# main.net
KiCad netlist of a schematic drawn in EAGLE
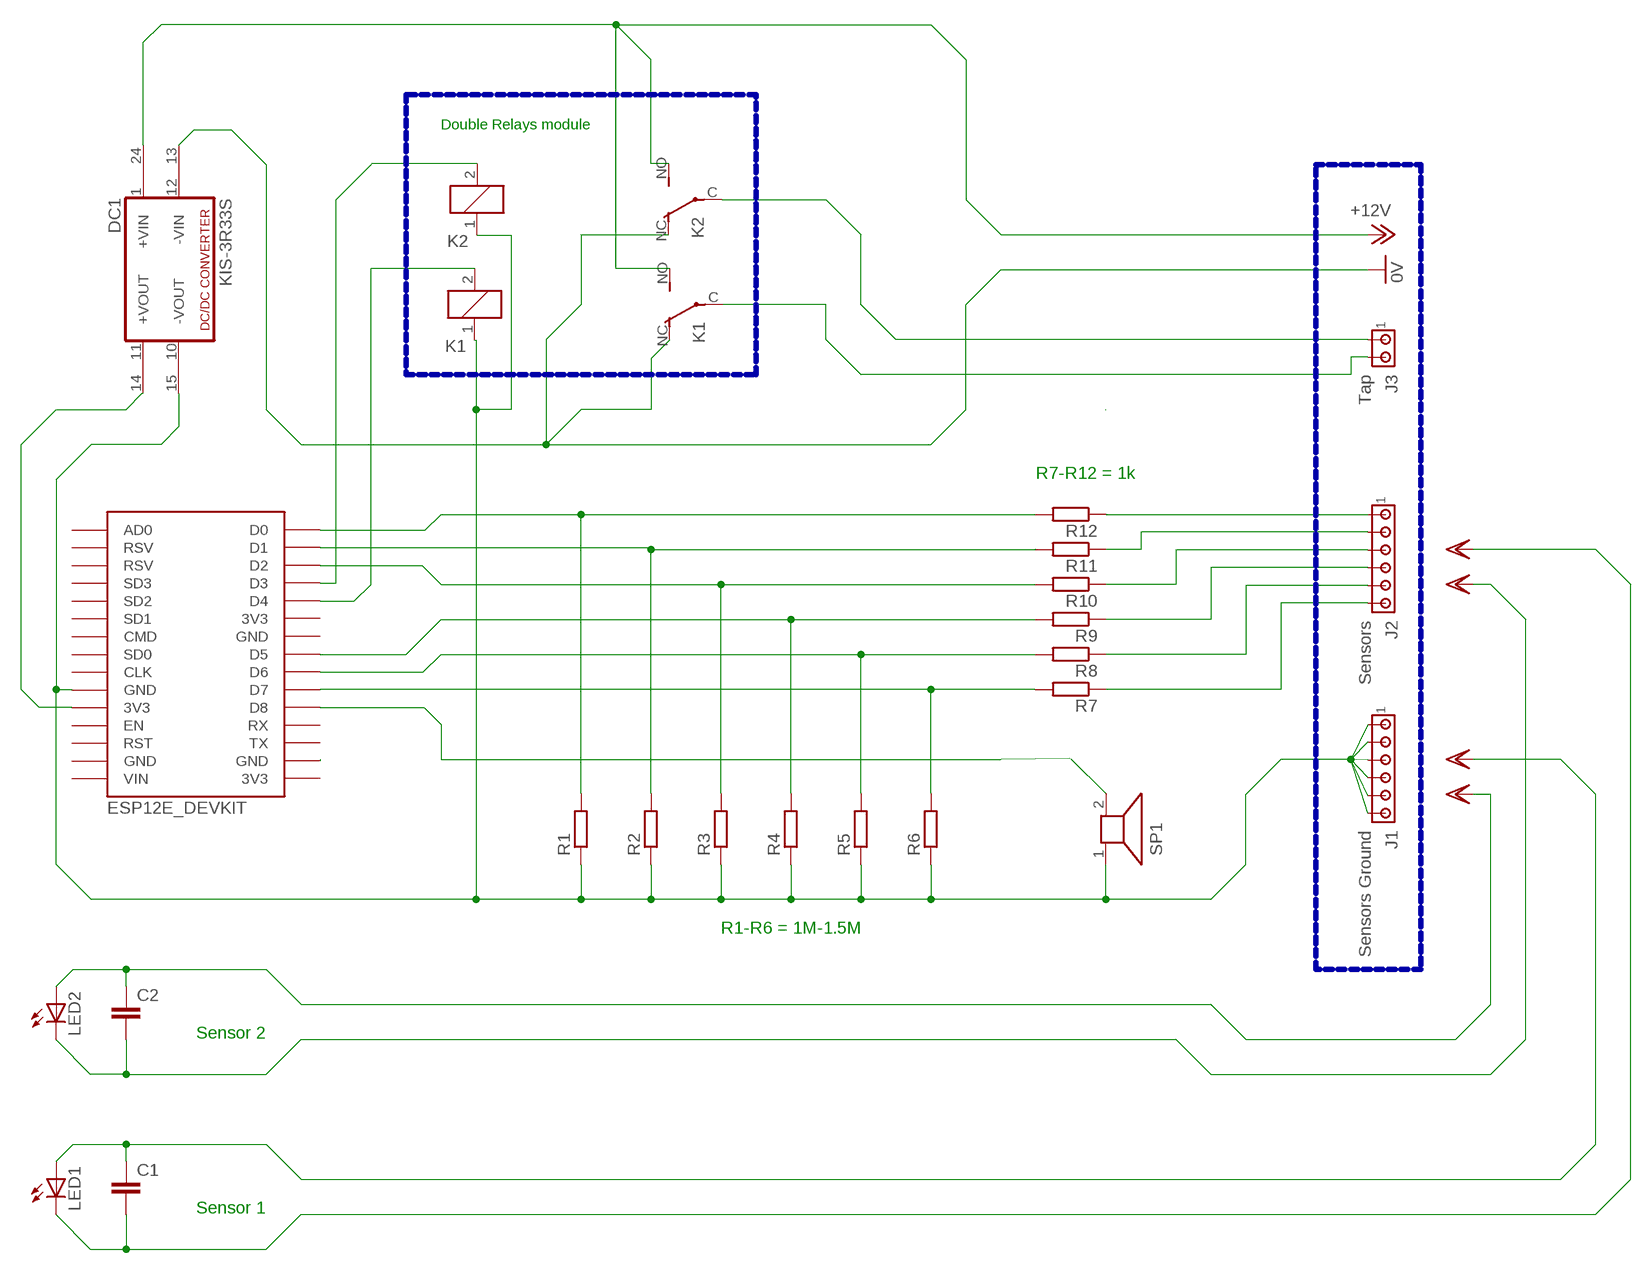
[diagram p0: schematic, sheet 1]

(export (version "E")
  (design (tool "Eeschema 10.0.6"))
  (components
    (comp (ref "C1")
      (value "C2,5-3")
      (footprint "eagle-import:C2.5-3")
      (libsource (lib "eagle-import") (part "C2,5-3"))
    )
    (comp (ref "C2")
      (value "C2,5-3")
      (footprint "eagle-import:C2.5-3")
      (libsource (lib "eagle-import") (part "C2,5-3"))
    )
    (comp (ref "DC1")
      (value "KIS-3R33S")
      (footprint "eagle-import:CMK")
      (libsource (lib "eagle-import") (part "DC213R"))
    )
    (comp (ref "J1")
      (value "Sensors Ground")
      (footprint "eagle-import:1X6MTA")
      (libsource (lib "eagle-import") (part "MTA06-156"))
    )
    (comp (ref "J2")
      (value "Sensors")
      (footprint "eagle-import:1X6MTA")
      (libsource (lib "eagle-import") (part "MTA06-156"))
    )
    (comp (ref "J3")
      (value "Tap")
      (footprint "eagle-import:1X2MTA")
      (libsource (lib "eagle-import") (part "MTA02-156"))
    )
    (comp (ref "K1")
      (value "CT112")
      (footprint "eagle-import:CT-SLIM")
      (libsource (lib "eagle-import") (part "CT112"))
    )
    (comp (ref "K2")
      (value "CT112")
      (footprint "eagle-import:CT-SLIM")
      (libsource (lib "eagle-import") (part "CT112"))
    )
    (comp (ref "LED1")
      (value "TLLG4400")
      (footprint "eagle-import:LED3MM")
      (fields (field (name "MF") "VISHAY SEMICONDUCTOR"))
      (libsource (lib "eagle-import") (part "TLLG4400"))
    )
    (comp (ref "LED2")
      (value "TLLG4400")
      (footprint "eagle-import:LED3MM")
      (fields (field (name "MF") "VISHAY SEMICONDUCTOR"))
      (libsource (lib "eagle-import") (part "TLLG4400"))
    )
    (comp (ref "R1")
      (value "R-EU_0204/7")
      (footprint "eagle-import:0204_7")
      (libsource (lib "eagle-import") (part "R-EU_0204/7"))
    )
    (comp (ref "R2")
      (value "R-EU_0204/7")
      (footprint "eagle-import:0204_7")
      (libsource (lib "eagle-import") (part "R-EU_0204/7"))
    )
    (comp (ref "R3")
      (value "R-EU_0204/7")
      (footprint "eagle-import:0204_7")
      (libsource (lib "eagle-import") (part "R-EU_0204/7"))
    )
    (comp (ref "R4")
      (value "R-EU_0204/7")
      (footprint "eagle-import:0204_7")
      (libsource (lib "eagle-import") (part "R-EU_0204/7"))
    )
    (comp (ref "R5")
      (value "R-EU_0204/7")
      (footprint "eagle-import:0204_7")
      (libsource (lib "eagle-import") (part "R-EU_0204/7"))
    )
    (comp (ref "R6")
      (value "R-EU_0204/7")
      (footprint "eagle-import:0204_7")
      (libsource (lib "eagle-import") (part "R-EU_0204/7"))
    )
    (comp (ref "R7")
      (value "R-EU_0204/7")
      (footprint "eagle-import:0204_7")
      (libsource (lib "eagle-import") (part "R-EU_0204/7"))
    )
    (comp (ref "R8")
      (value "R-EU_0204/7")
      (footprint "eagle-import:0204_7")
      (libsource (lib "eagle-import") (part "R-EU_0204/7"))
    )
    (comp (ref "R9")
      (value "R-EU_0204/7")
      (footprint "eagle-import:0204_7")
      (libsource (lib "eagle-import") (part "R-EU_0204/7"))
    )
    (comp (ref "R10")
      (value "R-EU_0204/7")
      (footprint "eagle-import:0204_7")
      (libsource (lib "eagle-import") (part "R-EU_0204/7"))
    )
    (comp (ref "R11")
      (value "R-EU_0204/7")
      (footprint "eagle-import:0204_7")
      (libsource (lib "eagle-import") (part "R-EU_0204/7"))
    )
    (comp (ref "R12")
      (value "R-EU_0204/7")
      (footprint "eagle-import:0204_7")
      (libsource (lib "eagle-import") (part "R-EU_0204/7"))
    )
    (comp (ref "SP1")
      (value "AL30P")
      (footprint "eagle-import:AL30P")
      (libsource (lib "eagle-import") (part "AL30P"))
    )
    (comp (ref "U$1")
      (value "ESP12E_DEVKIT")
      (footprint "eagle-import:ESP12E_DEVKIT")
      (libsource (lib "eagle-import") (part "ESP12E_DEVKIT"))
    )
  )
  (nets
    (net (code "1") (name "+12V") (class "Default")
      (node (ref "DC1") (pin "24") (pinfunction "+VIN1_24") (pintype "passive"))
      (node (ref "K1") (pin "NO") (pinfunction "S_NO") (pintype "passive"))
      (node (ref "K2") (pin "NO") (pinfunction "S_NO") (pintype "passive"))
    )
    (net (code "2") (name "0V") (class "Default")
      (node (ref "DC1") (pin "13") (pinfunction "-VIN1_13") (pintype "passive"))
      (node (ref "K1") (pin "NC") (pinfunction "O_NC") (pintype "passive"))
      (node (ref "K2") (pin "NC") (pinfunction "O_NC") (pintype "passive"))
    )
    (net (code "3") (name "Net-(DC1-+VOUT1)") (class "Default")
      (node (ref "DC1") (pin "14") (pinfunction "+VOUT1_14") (pintype "passive"))
      (node (ref "U$1") (pin "3V3@0") (pinfunction "3V3_3V3@0") (pintype "bidirectional"))
    )
    (net (code "4") (name "Net-(DC1--VOUT1)") (class "Default")
      (node (ref "DC1") (pin "15") (pinfunction "-VOUT1_15") (pintype "passive"))
      (node (ref "J1") (pin "1") (pinfunction "1_1") (pintype "passive"))
      (node (ref "J1") (pin "2") (pinfunction "2_2") (pintype "passive"))
      (node (ref "J1") (pin "3") (pinfunction "3_3") (pintype "passive"))
      (node (ref "J1") (pin "4") (pinfunction "4_4") (pintype "passive"))
      (node (ref "J1") (pin "5") (pinfunction "5_5") (pintype "passive"))
      (node (ref "J1") (pin "6") (pinfunction "6_6") (pintype "passive"))
      (node (ref "K1") (pin "1") (pinfunction "1_1") (pintype "passive"))
      (node (ref "K2") (pin "1") (pinfunction "1_1") (pintype "passive"))
      (node (ref "R1") (pin "1") (pinfunction "1_1") (pintype "passive"))
      (node (ref "R2") (pin "1") (pinfunction "1_1") (pintype "passive"))
      (node (ref "R3") (pin "1") (pinfunction "1_1") (pintype "passive"))
      (node (ref "R4") (pin "1") (pinfunction "1_1") (pintype "passive"))
      (node (ref "R5") (pin "1") (pinfunction "1_1") (pintype "passive"))
      (node (ref "R6") (pin "1") (pinfunction "1_1") (pintype "passive"))
      (node (ref "SP1") (pin "1") (pinfunction "1_1") (pintype "passive"))
      (node (ref "U$1") (pin "GND@0") (pinfunction "GND_GND@0") (pintype "bidirectional"))
    )
    (net (code "5") (name "Net-(J2-Pad1)") (class "Default")
      (node (ref "J2") (pin "1") (pinfunction "1_1") (pintype "passive"))
      (node (ref "R12") (pin "1") (pinfunction "1_1") (pintype "passive"))
    )
    (net (code "6") (name "Net-(J2-Pad2)") (class "Default")
      (node (ref "J2") (pin "2") (pinfunction "2_2") (pintype "passive"))
      (node (ref "R11") (pin "1") (pinfunction "1_1") (pintype "passive"))
    )
    (net (code "7") (name "Net-(J2-Pad3)") (class "Default")
      (node (ref "J2") (pin "3") (pinfunction "3_3") (pintype "passive"))
      (node (ref "R10") (pin "1") (pinfunction "1_1") (pintype "passive"))
    )
    (net (code "8") (name "Net-(J2-Pad4)") (class "Default")
      (node (ref "J2") (pin "4") (pinfunction "4_4") (pintype "passive"))
      (node (ref "R9") (pin "1") (pinfunction "1_1") (pintype "passive"))
    )
    (net (code "9") (name "Net-(J2-Pad5)") (class "Default")
      (node (ref "J2") (pin "5") (pinfunction "5_5") (pintype "passive"))
      (node (ref "R8") (pin "1") (pinfunction "1_1") (pintype "passive"))
    )
    (net (code "10") (name "Net-(J2-Pad6)") (class "Default")
      (node (ref "J2") (pin "6") (pinfunction "6_6") (pintype "passive"))
      (node (ref "R7") (pin "1") (pinfunction "1_1") (pintype "passive"))
    )
    (net (code "11") (name "Net-(K1-Pad2)") (class "Default")
      (node (ref "K1") (pin "2") (pinfunction "2_2") (pintype "passive"))
      (node (ref "U$1") (pin "D4") (pinfunction "D4_D4") (pintype "bidirectional"))
    )
    (net (code "12") (name "Net-(K1B-P)") (class "Default")
      (node (ref "J3") (pin "2") (pinfunction "2_2") (pintype "passive"))
      (node (ref "K1") (pin "C") (pinfunction "P_C") (pintype "passive"))
    )
    (net (code "13") (name "Net-(K2-Pad2)") (class "Default")
      (node (ref "K2") (pin "2") (pinfunction "2_2") (pintype "passive"))
      (node (ref "U$1") (pin "D3") (pinfunction "D3_D3") (pintype "bidirectional"))
    )
    (net (code "14") (name "Net-(K2B-P)") (class "Default")
      (node (ref "J3") (pin "1") (pinfunction "1_1") (pintype "passive"))
      (node (ref "K2") (pin "C") (pinfunction "P_C") (pintype "passive"))
    )
    (net (code "15") (name "Net-(R1-Pad2)") (class "Default")
      (node (ref "R1") (pin "2") (pinfunction "2_2") (pintype "passive"))
      (node (ref "R12") (pin "2") (pinfunction "2_2") (pintype "passive"))
      (node (ref "U$1") (pin "D0") (pinfunction "D0_D0") (pintype "bidirectional"))
    )
    (net (code "16") (name "Net-(R4-Pad2)") (class "Default")
      (node (ref "R4") (pin "2") (pinfunction "2_2") (pintype "passive"))
      (node (ref "R9") (pin "2") (pinfunction "2_2") (pintype "passive"))
      (node (ref "U$1") (pin "D5") (pinfunction "D5_D5") (pintype "bidirectional"))
    )
    (net (code "17") (name "Net-(R5-Pad2)") (class "Default")
      (node (ref "R5") (pin "2") (pinfunction "2_2") (pintype "passive"))
      (node (ref "R8") (pin "2") (pinfunction "2_2") (pintype "passive"))
      (node (ref "U$1") (pin "D6") (pinfunction "D6_D6") (pintype "bidirectional"))
    )
    (net (code "18") (name "Net-(R6-Pad2)") (class "Default")
      (node (ref "R6") (pin "2") (pinfunction "2_2") (pintype "passive"))
      (node (ref "R7") (pin "2") (pinfunction "2_2") (pintype "passive"))
      (node (ref "U$1") (pin "D7") (pinfunction "D7_D7") (pintype "bidirectional"))
    )
    (net (code "19") (name "Net-(R10-Pad2)") (class "Default")
      (node (ref "R10") (pin "2") (pinfunction "2_2") (pintype "passive"))
      (node (ref "R3") (pin "2") (pinfunction "2_2") (pintype "passive"))
      (node (ref "U$1") (pin "D2") (pinfunction "D2_D2") (pintype "bidirectional"))
    )
    (net (code "20") (name "Net-(R11-Pad2)") (class "Default")
      (node (ref "R11") (pin "2") (pinfunction "2_2") (pintype "passive"))
      (node (ref "R2") (pin "2") (pinfunction "2_2") (pintype "passive"))
      (node (ref "U$1") (pin "D1") (pinfunction "D1_D1") (pintype "bidirectional"))
    )
    (net (code "21") (name "VDD") (class "Default")
      (node (ref "C1") (pin "2") (pinfunction "2_2") (pintype "passive"))
      (node (ref "C2") (pin "2") (pinfunction "2_2") (pintype "passive"))
      (node (ref "LED1") (pin "K") (pinfunction "C_K") (pintype "passive"))
      (node (ref "LED2") (pin "K") (pinfunction "C_K") (pintype "passive"))
    )
    (net (code "22") (name "VSS") (class "Default")
      (node (ref "C1") (pin "1") (pinfunction "1_1") (pintype "passive"))
      (node (ref "C2") (pin "1") (pinfunction "1_1") (pintype "passive"))
      (node (ref "LED1") (pin "A") (pinfunction "A_A") (pintype "passive"))
      (node (ref "LED2") (pin "A") (pinfunction "A_A") (pintype "passive"))
    )
    (net (code "23") (name "unconnected-(DC1-+VIN-Pad1)") (class "Default")
      (node (ref "DC1") (pin "1") (pinfunction "+VIN_1") (pintype "passive"))
    )
    (net (code "24") (name "unconnected-(DC1-+VOUT-Pad11)") (class "Default")
      (node (ref "DC1") (pin "11") (pinfunction "+VOUT_11") (pintype "passive"))
    )
    (net (code "25") (name "unconnected-(DC1--VIN-Pad12)") (class "Default")
      (node (ref "DC1") (pin "12") (pinfunction "-VIN_12") (pintype "passive"))
    )
    (net (code "26") (name "unconnected-(DC1--VOUT-Pad10)") (class "Default")
      (node (ref "DC1") (pin "10") (pinfunction "-VOUT_10") (pintype "passive"))
    )
    (net (code "27") (name "unconnected-(SP1-Pad2)") (class "Default")
      (node (ref "SP1") (pin "2") (pinfunction "2_2") (pintype "passive"))
    )
    (net (code "28") (name "unconnected-(U$1-3V3-Pad3V3@1)") (class "Default")
      (node (ref "U$1") (pin "3V3@1") (pinfunction "3V3_3V3@1") (pintype "bidirectional"))
    )
    (net (code "29") (name "unconnected-(U$1-3V3-Pad3V3@2)") (class "Default")
      (node (ref "U$1") (pin "3V3@2") (pinfunction "3V3_3V3@2") (pintype "bidirectional"))
    )
    (net (code "30") (name "unconnected-(U$1-GND-PadGND@1)") (class "Default")
      (node (ref "U$1") (pin "GND@1") (pinfunction "GND_GND@1") (pintype "bidirectional"))
    )
    (net (code "31") (name "unconnected-(U$1-GND-PadGND@2)") (class "Default")
      (node (ref "U$1") (pin "GND@2") (pinfunction "GND_GND@2") (pintype "bidirectional"))
    )
    (net (code "32") (name "unconnected-(U$1-GND-PadGND@3)") (class "Default")
      (node (ref "U$1") (pin "GND@3") (pinfunction "GND_GND@3") (pintype "bidirectional"))
    )
    (net (code "33") (name "unconnected-(U$1-PadAD0)") (class "Default")
      (node (ref "U$1") (pin "AD0") (pinfunction "AD0_AD0") (pintype "bidirectional"))
    )
    (net (code "34") (name "unconnected-(U$1-PadCLK)") (class "Default")
      (node (ref "U$1") (pin "CLK") (pinfunction "CLK_CLK") (pintype "bidirectional"))
    )
    (net (code "35") (name "unconnected-(U$1-PadCMD)") (class "Default")
      (node (ref "U$1") (pin "CMD") (pinfunction "CMD_CMD") (pintype "bidirectional"))
    )
    (net (code "36") (name "unconnected-(U$1-PadD8)") (class "Default")
      (node (ref "U$1") (pin "D8") (pinfunction "D8_D8") (pintype "bidirectional"))
    )
    (net (code "37") (name "unconnected-(U$1-PadEN)") (class "Default")
      (node (ref "U$1") (pin "EN") (pinfunction "EN_EN") (pintype "bidirectional"))
    )
    (net (code "38") (name "unconnected-(U$1-PadRST)") (class "Default")
      (node (ref "U$1") (pin "RST") (pinfunction "RST_RST") (pintype "bidirectional"))
    )
    (net (code "39") (name "unconnected-(U$1-PadRX)") (class "Default")
      (node (ref "U$1") (pin "RX") (pinfunction "RX_RX") (pintype "bidirectional"))
    )
    (net (code "40") (name "unconnected-(U$1-PadSD0)") (class "Default")
      (node (ref "U$1") (pin "SD0") (pinfunction "SD0_SD0") (pintype "bidirectional"))
    )
    (net (code "41") (name "unconnected-(U$1-PadSD1)") (class "Default")
      (node (ref "U$1") (pin "SD1") (pinfunction "SD1_SD1") (pintype "bidirectional"))
    )
    (net (code "42") (name "unconnected-(U$1-PadSD2)") (class "Default")
      (node (ref "U$1") (pin "SD2") (pinfunction "SD2_SD2") (pintype "bidirectional"))
    )
    (net (code "43") (name "unconnected-(U$1-PadSD3)") (class "Default")
      (node (ref "U$1") (pin "SD3") (pinfunction "SD3_SD3") (pintype "bidirectional"))
    )
    (net (code "44") (name "unconnected-(U$1-PadTX)") (class "Default")
      (node (ref "U$1") (pin "TX") (pinfunction "TX_TX") (pintype "bidirectional"))
    )
    (net (code "45") (name "unconnected-(U$1-PadVIN)") (class "Default")
      (node (ref "U$1") (pin "VIN") (pinfunction "VIN_VIN") (pintype "bidirectional"))
    )
    (net (code "46") (name "unconnected-(U$1-RSV-PadRSV@0)") (class "Default")
      (node (ref "U$1") (pin "RSV@0") (pinfunction "RSV_RSV@0") (pintype "bidirectional"))
    )
    (net (code "47") (name "unconnected-(U$1-RSV-PadRSV@1)") (class "Default")
      (node (ref "U$1") (pin "RSV@1") (pinfunction "RSV_RSV@1") (pintype "bidirectional"))
    )
  )
)
